# EMGfrontend.net
KiCad netlist of a schematic drawn in Altium Designer
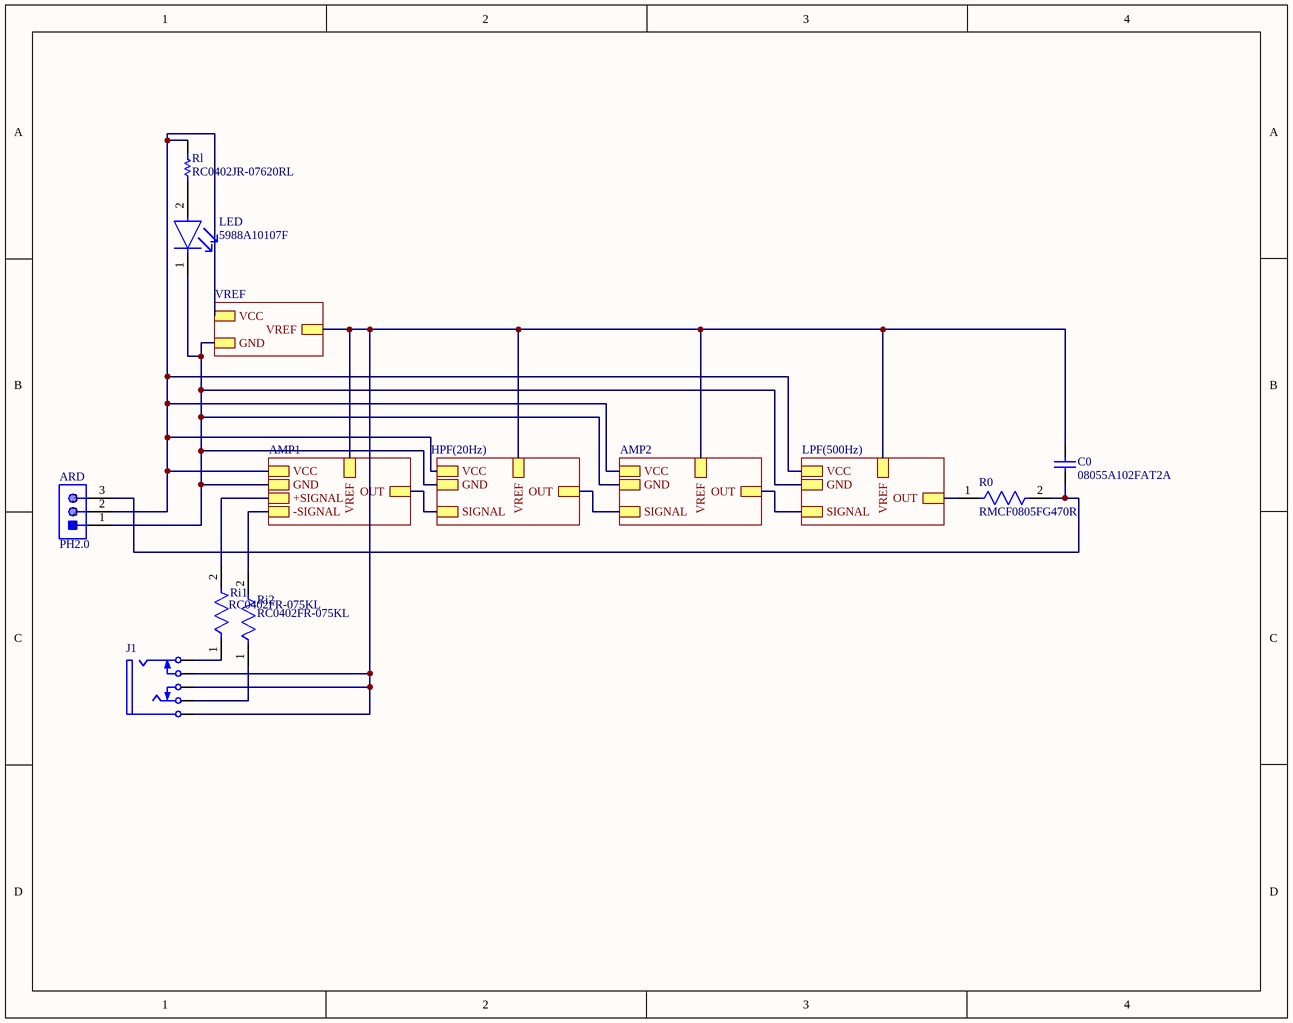
[diagram p0: EMGfrontend.SchDoc]

(export (version "E")
  (design (tool "Eeschema 10.0.6"))
  (components
    (comp (ref "ARD")
      (value "PH2.0")
      (footprint "JST-B3B-PH-K-S-3_V")
      (fields (field (name "MANUFACTURER") "JST"))
      (libsource (lib "Altium Content Vault") (part "CN-1P-M-R3"))
    )
    (comp (ref "C0")
      (value "08055A102FAT2A")
      (footprint "CAPC2013X94X50NL20T25")
      (fields (field (name "MANUFACTURER") "AVX Interconnect / Elco"))
      (libsource (lib "Altium Content Vault") (part "CAP"))
    )
    (comp (ref "J1")
      (value "~")
      (footprint "SWIT-35RASMT4BHNTRX_V")
      (description "Female 3.5 mm Phone Jack, 5 Position, Height 5 mm, RoHS, Tape and Reel")
      (libsource (lib "Altium Content Vault") (part "JACK-3CD5-RN"))
    )
    (comp (ref "LED")
      (value "5988A10107F")
      (footprint "FP-5988A10107F-MFG")
      (description "5988A10107F LED Uni-Color Red 2-Pin Chip 0402(1006Metric) T/R")
      (libsource (lib "Altium Content Vault") (part "8706943c75ba83719d021d2fdc84c58"))
    )
    (comp (ref "R0")
      (value "RMCF0805FG470R")
      (footprint "FP-RMCF0805-IPC_C")
      (description "470Ω ±1% 0.125W 0805 Thick Film Chip Resistor AEC-Q200 compliant")
      (fields (field (name "TOLERANCE") "1%"))
      (libsource (lib "Altium Content Vault") (part "1029c3af85768c4190bb7ad29bc67b5"))
    )
    (comp (ref "Ri1")
      (value "RC0402FR-075KL")
      (footprint "FP-RC0402-MFG")
      (description "RES SMD 5K OHM 1% 1/16W 0402")
      (fields (field (name "MANUFACTURER") "Yageo") (field (name "TOLERANCE") "1%"))
      (libsource (lib "Altium Content Vault") (part "1029c3af85768c4190bb7ad29bc67b5"))
    )
    (comp (ref "Ri2")
      (value "RC0402FR-075KL")
      (footprint "FP-RC0402-MFG")
      (description "RES SMD 5K OHM 1% 1/16W 0402")
      (fields (field (name "MANUFACTURER") "Yageo") (field (name "TOLERANCE") "1%"))
      (libsource (lib "Altium Content Vault") (part "1029c3af85768c4190bb7ad29bc67b5"))
    )
    (comp (ref "Rl")
      (value "RC0402JR-07620RL")
      (footprint "RESC1005X40X25ML05T10")
      (fields (field (name "MANUFACTURER") "Yageo / Phycomp"))
      (libsource (lib "Altium Content Vault") (part "RES"))
    )
  )
  (nets
    (net (code "1") (name "/+SIGNAL") (class "Default")
      (node (ref "Ri1") (pin "2") (pinfunction "2_2") (pintype "passive"))
    )
    (net (code "2") (name "/-SIGNAL") (class "Default")
      (node (ref "Ri2") (pin "2") (pinfunction "2_2") (pintype "passive"))
    )
    (net (code "3") (name "/GND") (class "Default")
      (node (ref "ARD") (pin "1") (pinfunction "1_1") (pintype "passive"))
      (node (ref "LED") (pin "1") (pinfunction "C_1") (pintype "passive"))
    )
    (net (code "7") (name "/OUT_3") (class "Default")
      (node (ref "R0") (pin "1") (pinfunction "1_1") (pintype "passive"))
    )
    (net (code "8") (name "/VCC") (class "Default")
      (node (ref "ARD") (pin "2") (pinfunction "2_2") (pintype "passive"))
      (node (ref "Rl") (pin "2") (pinfunction "2_2") (pintype "passive"))
    )
    (net (code "9") (name "/VREF") (class "Default")
      (node (ref "C0") (pin "2") (pinfunction "2_2") (pintype "passive"))
      (node (ref "J1") (pin "1") (pinfunction "1_1") (pintype "passive"))
      (node (ref "J1") (pin "4") (pinfunction "4_4") (pintype "passive"))
      (node (ref "J1") (pin "5") (pinfunction "5_5") (pintype "passive"))
    )
    (net (code "10") (name "Net-(ARD-Pad3)") (class "Default")
      (node (ref "ARD") (pin "3") (pinfunction "3_3") (pintype "passive"))
      (node (ref "C0") (pin "1") (pinfunction "1_1") (pintype "passive"))
      (node (ref "R0") (pin "2") (pinfunction "2_2") (pintype "passive"))
    )
    (net (code "11") (name "Net-(J1-Pad2)") (class "Default")
      (node (ref "J1") (pin "2") (pinfunction "2_2") (pintype "passive"))
      (node (ref "Ri1") (pin "1") (pinfunction "1_1") (pintype "passive"))
    )
    (net (code "12") (name "Net-(J1-Pad3)") (class "Default")
      (node (ref "J1") (pin "3") (pinfunction "3_3") (pintype "passive"))
      (node (ref "Ri2") (pin "1") (pinfunction "1_1") (pintype "passive"))
    )
    (net (code "13") (name "Net-(LED-A)") (class "Default")
      (node (ref "LED") (pin "2") (pinfunction "A_2") (pintype "passive"))
      (node (ref "Rl") (pin "1") (pinfunction "1_1") (pintype "passive"))
    )
  )
)
